# LeoBlinky2018.net
KiCad netlist of a schematic drawn in Altium Designer
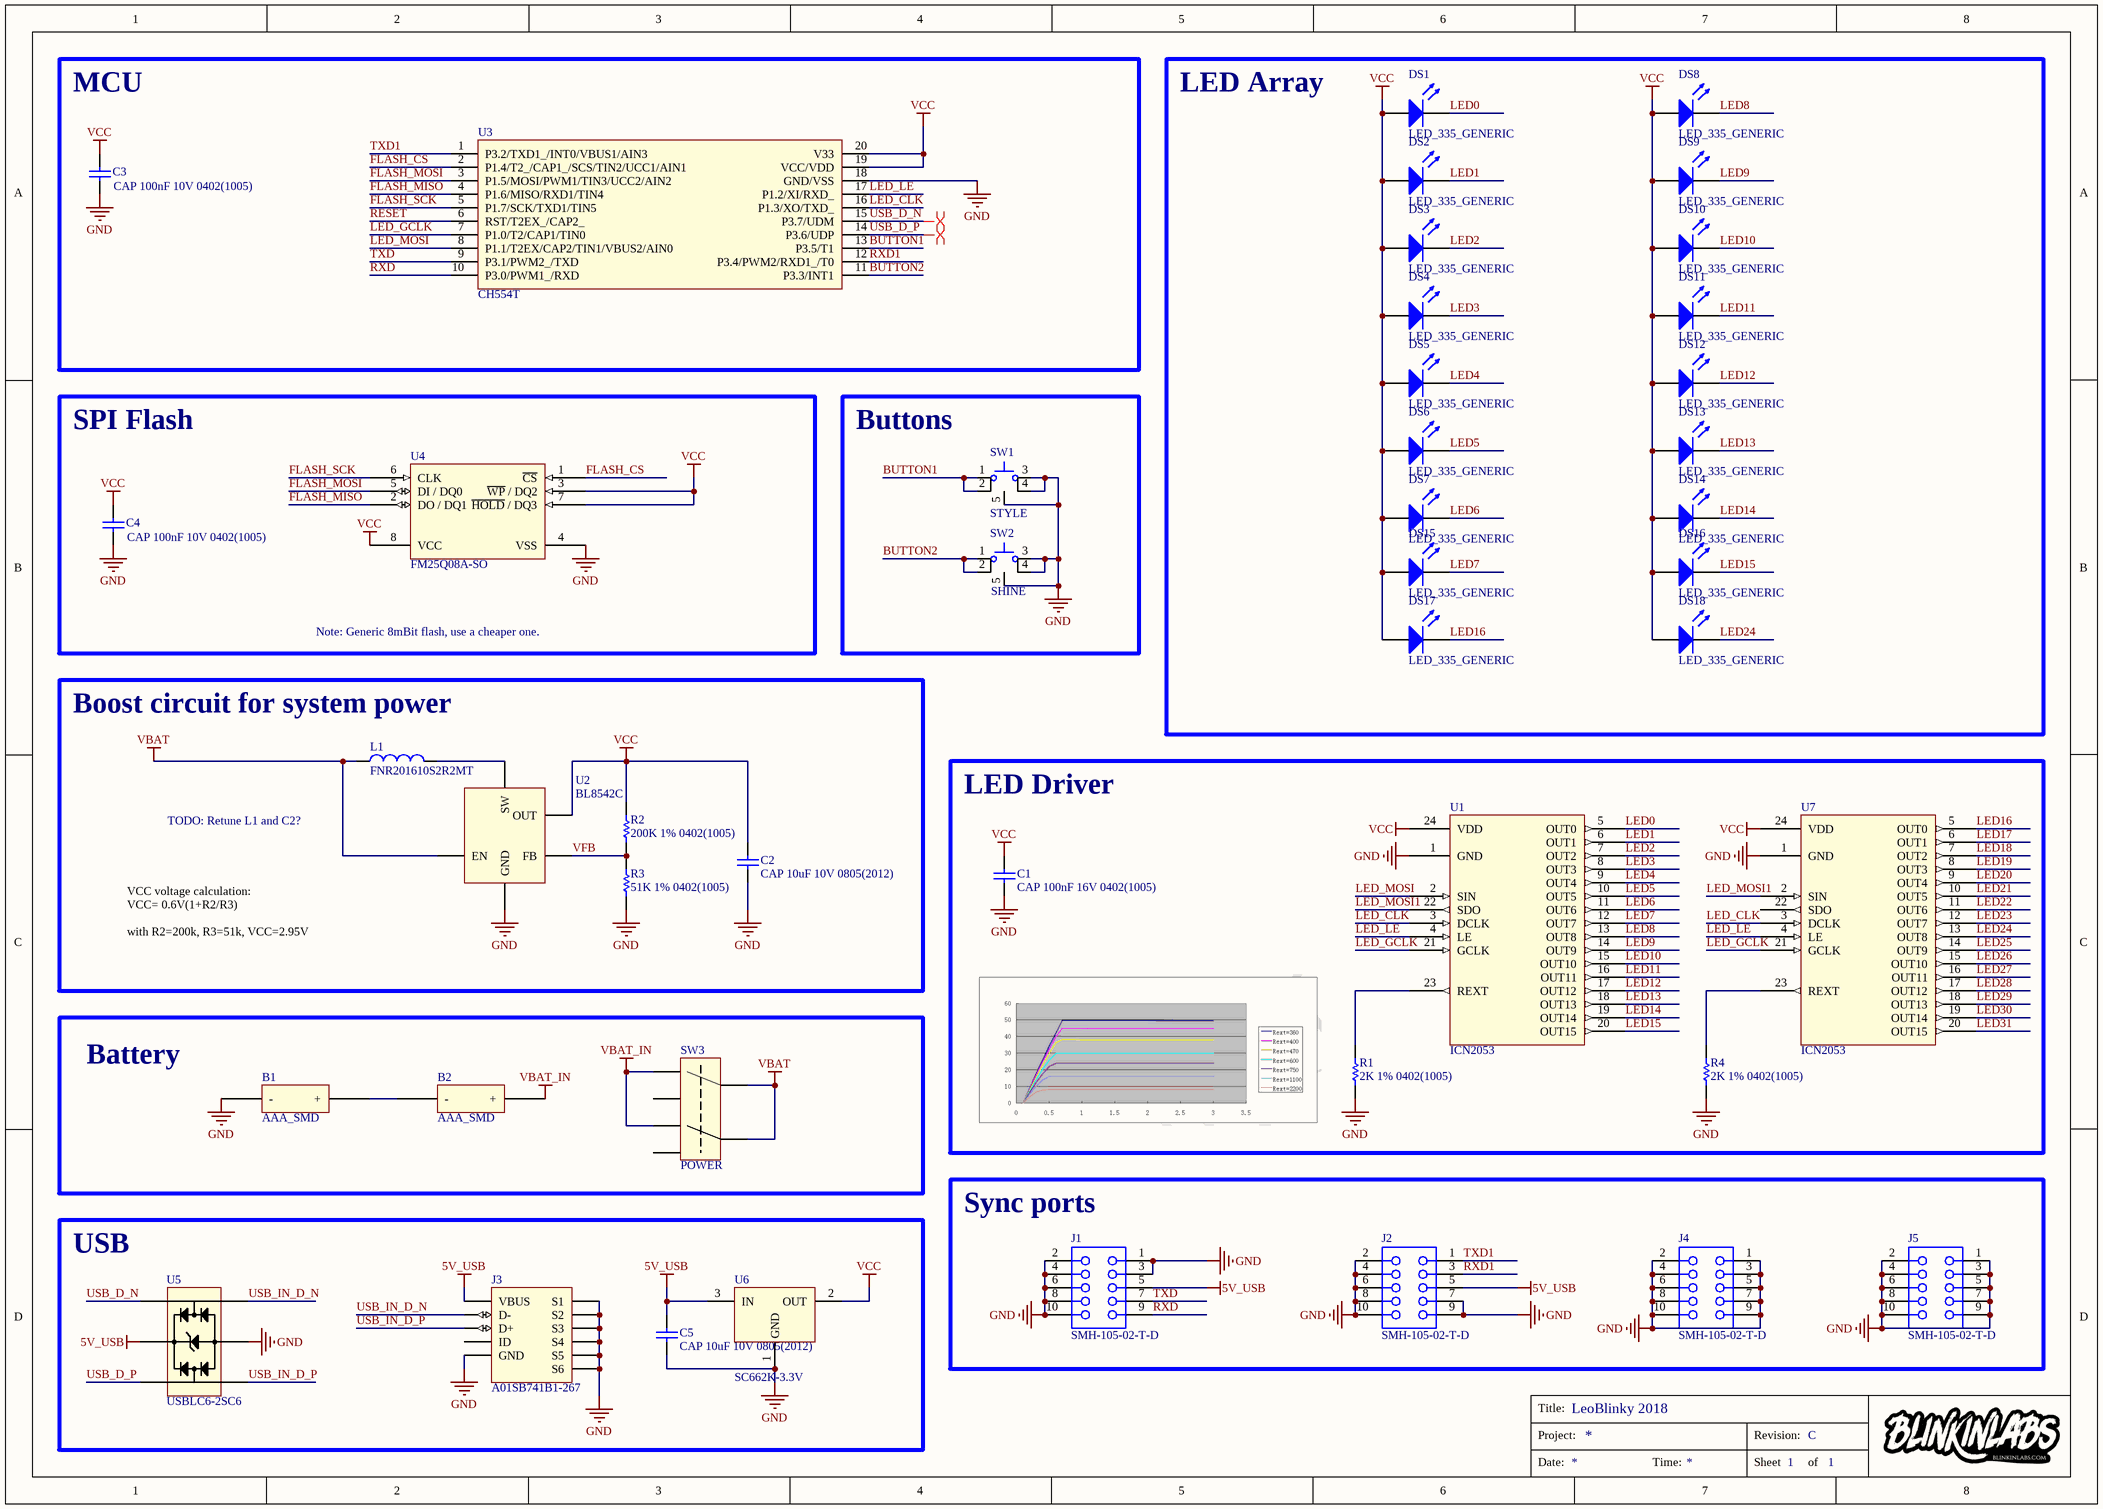
[diagram p0: LeoBlinky2018.SchDoc]

(export (version "E")
  (design (tool "Eeschema 10.0.6"))
  (components
    (comp (ref "B1")
      (value "AAA_SMD")
      (footprint "AAA_SMD")
      (description "AAA battery holder, surface mount.")
      (libsource (lib "Blinkinlabs") (part "AAA_SMD"))
    )
    (comp (ref "B2")
      (value "AAA_SMD")
      (footprint "AAA_SMD")
      (description "AAA battery holder, surface mount.")
      (libsource (lib "Blinkinlabs") (part "AAA_SMD"))
    )
    (comp (ref "C1")
      (value "CAP 100nF 16V 0402(1005)")
      (footprint "CAPC0402(1005)60_N")
      (description "CAP 100nF 16V -20% to +80% 0402 (1005 Metric) Thickness 0.6mm SMD")
      (fields (field (name "TOLERANCE") "-20% to +80%"))
      (libsource (lib "Altium Content Vault") (part "CAP"))
    )
    (comp (ref "C2")
      (value "CAP 10uF 10V 0805(2012)")
      (footprint "CAPC0805(2012)145_N")
      (description "CAP 10uF 10V ±10% 0805 (2012 Metric) Thickness 1.45mm SMD")
      (fields (field (name "TOLERANCE") "Â±10%"))
      (libsource (lib "Altium Content Vault") (part "CMP-1036-04922-1"))
    )
    (comp (ref "C3")
      (value "CAP 100nF 10V 0402(1005)")
      (footprint "CAPC0402(1005)60_L")
      (description "CAP 100nF 10V ±10% 0402 (1005 Metric) Thickness 0.6mm SMD")
      (fields (field (name "TOLERANCE") "Â±10%"))
      (libsource (lib "Altium Content Vault") (part "CMP-1034-02065-1"))
    )
    (comp (ref "C4")
      (value "CAP 100nF 10V 0402(1005)")
      (footprint "CAPC0402(1005)60_L")
      (description "CAP 100nF 10V ±10% 0402 (1005 Metric) Thickness 0.6mm SMD")
      (fields (field (name "TOLERANCE") "Â±10%"))
      (libsource (lib "Altium Content Vault") (part "CMP-1034-02065-1"))
    )
    (comp (ref "C5")
      (value "CAP 10uF 10V 0805(2012)")
      (footprint "CAPC0805(2012)145_N")
      (description "CAP 10uF 10V ±10% 0805 (2012 Metric) Thickness 1.45mm SMD")
      (fields (field (name "TOLERANCE") "Â±10%"))
      (libsource (lib "Altium Content Vault") (part "CAP"))
    )
    (comp (ref "DS1")
      (value "LED_335_GENERIC")
      (footprint "LED_335_GENERIC")
      (description "SMD LED, side visible, generic")
      (libsource (lib "Blinkinlabs") (part "LED_335_GENERIC"))
    )
    (comp (ref "DS2")
      (value "LED_335_GENERIC")
      (footprint "LED_335_GENERIC")
      (description "SMD LED, side visible, generic")
      (libsource (lib "Blinkinlabs") (part "LED_335_GENERIC"))
    )
    (comp (ref "DS3")
      (value "LED_335_GENERIC")
      (footprint "LED_335_GENERIC")
      (description "SMD LED, side visible, generic")
      (libsource (lib "Blinkinlabs") (part "LED_335_GENERIC"))
    )
    (comp (ref "DS4")
      (value "LED_335_GENERIC")
      (footprint "LED_335_GENERIC")
      (description "SMD LED, side visible, generic")
      (libsource (lib "Blinkinlabs") (part "LED_335_GENERIC"))
    )
    (comp (ref "DS5")
      (value "LED_335_GENERIC")
      (footprint "LED_335_GENERIC")
      (description "SMD LED, side visible, generic")
      (libsource (lib "Blinkinlabs") (part "LED_335_GENERIC"))
    )
    (comp (ref "DS6")
      (value "LED_335_GENERIC")
      (footprint "LED_335_GENERIC")
      (description "SMD LED, side visible, generic")
      (libsource (lib "Blinkinlabs") (part "LED_335_GENERIC"))
    )
    (comp (ref "DS7")
      (value "LED_335_GENERIC")
      (footprint "LED_335_GENERIC")
      (description "SMD LED, side visible, generic")
      (libsource (lib "Blinkinlabs") (part "LED_335_GENERIC"))
    )
    (comp (ref "DS8")
      (value "LED_335_GENERIC")
      (footprint "LED_335_GENERIC")
      (description "SMD LED, side visible, generic")
      (libsource (lib "Blinkinlabs") (part "LED_335_GENERIC"))
    )
    (comp (ref "DS9")
      (value "LED_335_GENERIC")
      (footprint "LED_335_GENERIC")
      (description "SMD LED, side visible, generic")
      (libsource (lib "Blinkinlabs") (part "LED_335_GENERIC"))
    )
    (comp (ref "DS10")
      (value "LED_335_GENERIC")
      (footprint "LED_335_GENERIC")
      (description "SMD LED, side visible, generic")
      (libsource (lib "Blinkinlabs") (part "LED_335_GENERIC"))
    )
    (comp (ref "DS11")
      (value "LED_335_GENERIC")
      (footprint "LED_335_GENERIC")
      (description "SMD LED, side visible, generic")
      (libsource (lib "Blinkinlabs") (part "LED_335_GENERIC"))
    )
    (comp (ref "DS12")
      (value "LED_335_GENERIC")
      (footprint "LED_335_GENERIC")
      (description "SMD LED, side visible, generic")
      (libsource (lib "Blinkinlabs") (part "LED_335_GENERIC"))
    )
    (comp (ref "DS13")
      (value "LED_335_GENERIC")
      (footprint "LED_335_GENERIC")
      (description "SMD LED, side visible, generic")
      (libsource (lib "Blinkinlabs") (part "LED_335_GENERIC"))
    )
    (comp (ref "DS14")
      (value "LED_335_GENERIC")
      (footprint "LED_335_GENERIC")
      (description "SMD LED, side visible, generic")
      (libsource (lib "Blinkinlabs") (part "LED_335_GENERIC"))
    )
    (comp (ref "DS15")
      (value "LED_335_GENERIC")
      (footprint "LED_335_GENERIC")
      (description "SMD LED, side visible, generic")
      (libsource (lib "Blinkinlabs") (part "LED_335_GENERIC"))
    )
    (comp (ref "DS16")
      (value "LED_335_GENERIC")
      (footprint "LED_335_GENERIC")
      (description "SMD LED, side visible, generic")
      (libsource (lib "Blinkinlabs") (part "LED_335_GENERIC"))
    )
    (comp (ref "DS17")
      (value "LED_335_GENERIC")
      (footprint "LED_335_GENERIC")
      (description "SMD LED, side visible, generic")
      (libsource (lib "Blinkinlabs") (part "LED_335_GENERIC"))
    )
    (comp (ref "DS18")
      (value "LED_335_GENERIC")
      (footprint "LED_335_GENERIC")
      (description "SMD LED, side visible, generic")
      (libsource (lib "Blinkinlabs") (part "LED_335_GENERIC"))
    )
    (comp (ref "J1")
      (value "SMH-105-02-T-D")
      (footprint "SMTC-SMH-105-02-X-D")
      (description "SMT Horizontal Socket, -55 to 105 degC, 2.54 mm Pitch, 10-Pin, Female, RoHS")
      (fields (field (name "MANUFACTURER") "Samtec"))
      (libsource (lib "Altium Content Vault") (part "SMTC-SMH-105-02-X-D-X"))
    )
    (comp (ref "J2")
      (value "SMH-105-02-T-D")
      (footprint "SMTC-SMH-105-02-X-D")
      (description "SMT Horizontal Socket, -55 to 105 degC, 2.54 mm Pitch, 10-Pin, Female, RoHS")
      (fields (field (name "MANUFACTURER") "Samtec"))
      (libsource (lib "Altium Content Vault") (part "SMTC-SMH-105-02-X-D-X"))
    )
    (comp (ref "J3")
      (value "A01SB741B1-267")
      (footprint "A01SB741B1-267")
      (description "Micro USB B type 四脚全插牛角")
      (libsource (lib "Blinkinlabs") (part "A01SB741B1-267"))
    )
    (comp (ref "J4")
      (value "SMH-105-02-T-D")
      (footprint "SMTC-SMH-105-02-X-D")
      (description "SMT Horizontal Socket, -55 to 105 degC, 2.54 mm Pitch, 10-Pin, Female, RoHS")
      (fields (field (name "MANUFACTURER") "Samtec"))
      (libsource (lib "Altium Content Vault") (part "SMTC-SMH-105-02-X-D-X"))
    )
    (comp (ref "J5")
      (value "SMH-105-02-T-D")
      (footprint "SMTC-SMH-105-02-X-D")
      (description "SMT Horizontal Socket, -55 to 105 degC, 2.54 mm Pitch, 10-Pin, Female, RoHS")
      (fields (field (name "MANUFACTURER") "Samtec"))
      (libsource (lib "Altium Content Vault") (part "SMTC-SMH-105-02-X-D-X"))
    )
    (comp (ref "L1")
      (value "FNR201610S2R2MT")
      (footprint "FNR201610S")
      (description "Wire Wound SMD Power Inductors 2.0×1.6×1.0 2.2uH")
      (libsource (lib "Blinkinlabs") (part "FNR201610S2R2MT"))
    )
    (comp (ref "R1")
      (value "2K 1% 0402(1005)")
      (footprint "RESC0402(1005)_N")
      (description "2K 0.063W 1% 0402 (1005 Metric)  SMD")
      (fields (field (name "POWER") "0.063 W") (field (name "TOLERANCE") "1 %"))
      (libsource (lib "Altium Content Vault") (part "RES"))
    )
    (comp (ref "R2")
      (value "200K 1% 0402(1005)")
      (footprint "RESC0402(1005)_L")
      (description "200K 0.063W 1% 0402 (1005 Metric)  SMD")
      (fields (field (name "TOLERANCE") "1 %") (field (name "POWER") "0.063 W"))
      (libsource (lib "Altium Content Vault") (part "RES"))
    )
    (comp (ref "R3")
      (value "51K 1% 0402(1005)")
      (footprint "RESC0402(1005)_L")
      (description "51K 0.063W 1% 0402 (1005 Metric)  SMD")
      (fields (field (name "TOLERANCE") "1 %") (field (name "POWER") "0.063 W"))
      (libsource (lib "Altium Content Vault") (part "RES"))
    )
    (comp (ref "R4")
      (value "2K 1% 0402(1005)")
      (footprint "RESC0402(1005)_N")
      (description "2K 0.063W 1% 0402 (1005 Metric)  SMD")
      (fields (field (name "POWER") "0.063 W") (field (name "TOLERANCE") "1 %"))
      (libsource (lib "Altium Content Vault") (part "RES"))
    )
    (comp (ref "SW1")
      (value "STYLE")
      (footprint "TD-07XB")
      (description "Tact Switch")
      (fields
        (field (name "MANUFACTURER") "ShenZhen XieJia Electronics Co Ltd")
        (field (name "PARTNUMBER") "TD-07XB")
      )
      (libsource (lib "Blinkinlabs") (part "TD-07XB"))
    )
    (comp (ref "SW2")
      (value "SHINE")
      (footprint "TD-07XB")
      (description "Tact Switch")
      (fields
        (field (name "MANUFACTURER") "ShenZhen XieJia Electronics Co Ltd")
        (field (name "PARTNUMBER") "TD-07XB")
      )
      (libsource (lib "Blinkinlabs") (part "TD-07XB"))
    )
    (comp (ref "SW3")
      (value "POWER")
      (footprint "MSK-1133-NOHOLE")
      (description "SMD micro toggle switch, 2 position, 2 circuit")
      (libsource (lib "Blinkinlabs") (part "MSK-1133"))
    )
    (comp (ref "U1")
      (value "ICN2053")
      (footprint "SOP64P600X175-24N")
      (description "16-Channel PWM Constant Current LED Sink Driver")
      (fields (field (name "MANUFACTURER") "ChipOne"))
      (libsource (lib "Blinkinlabs") (part "ICN2053"))
    )
    (comp (ref "U2")
      (value "BL8542C")
      (footprint "SOT95P280X130-5N")
      (description "0.85V startup, 1MHz, 300mA Iout,  Synchronous Boost Converter (adjustable output)")
      (fields (field (name "MANUFACTURER") "Belling"))
      (libsource (lib "Blinkinlabs") (part "BL8542C"))
    )
    (comp (ref "U3")
      (value "CH554T")
      (footprint "TSOP65P660X110-20N")
      (description "8-bit enhanced USB microcontroller")
      (fields (field (name "MANUFACTURER") "WCH"))
      (libsource (lib "Blinkinlabs") (part "CH554T"))
    )
    (comp (ref "U4")
      (value "FM25Q08A-SO")
      (footprint "SOP127P600X175-8N")
      (description "8M-BIT SERIAL FLASH MEMORY, 150mil width")
      (fields (field (name "MANUFACTURER") "Shanghai Fudan Microelectronics Group Company Limited"))
      (libsource (lib "Blinkinlabs") (part "FM25Q08A-SO"))
    )
    (comp (ref "U5")
      (value "USBLC6-2SC6")
      (footprint "SOT95P280X145-6N")
      (description "Very low capacitance ESD protection")
      (fields (field (name "MANUFACTURER") "STMicroelectronics"))
      (libsource (lib "Blinkinlabs") (part "USBLC6-2SC6"))
    )
    (comp (ref "U6")
      (value "SC662K-3.3V")
      (footprint "SOT95P230X117-3N")
      (description "3.3V, 250mA Low dropout voltage regulator IC")
      (libsource (lib "Blinkinlabs") (part "SC662K-3.3V"))
    )
    (comp (ref "U7")
      (value "ICN2053")
      (footprint "SOP64P600X175-24N")
      (description "16-Channel PWM Constant Current LED Sink Driver")
      (fields (field (name "MANUFACTURER") "ChipOne"))
      (libsource (lib "Blinkinlabs") (part "ICN2053"))
    )
  )
  (nets
    (net (code "1") (name "/BUTTON1") (class "Default")
      (node (ref "SW1") (pin "1") (pinfunction "1_1") (pintype "passive"))
      (node (ref "SW1") (pin "2") (pinfunction "2_2") (pintype "passive"))
      (node (ref "U3") (pin "13") (pinfunction "P3.5/T1_13") (pintype "passive"))
    )
    (net (code "2") (name "/BUTTON2") (class "Default")
      (node (ref "SW2") (pin "1") (pinfunction "1_1") (pintype "passive"))
      (node (ref "SW2") (pin "2") (pinfunction "2_2") (pintype "passive"))
      (node (ref "U3") (pin "11") (pinfunction "P3.3/INT1_11") (pintype "passive"))
    )
    (net (code "3") (name "/FLASH_CS") (class "Default")
      (node (ref "U3") (pin "2") (pinfunction "P1.4/T2_/CAP1_/SCS/TIN2/UCC1/AIN1_2") (pintype "passive"))
      (node (ref "U4") (pin "1") (pinfunction "~{CS}_1") (pintype "input"))
    )
    (net (code "4") (name "/FLASH_MISO") (class "Default")
      (node (ref "U3") (pin "4") (pinfunction "P1.6/MISO/RXD1/TIN4_4") (pintype "passive"))
      (node (ref "U4") (pin "2") (pinfunction "DO_/_DQ1_2") (pintype "bidirectional"))
    )
    (net (code "5") (name "/FLASH_MOSI") (class "Default")
      (node (ref "U3") (pin "3") (pinfunction "P1.5/MOSI/PWM1/TIN3/UCC2/AIN2_3") (pintype "passive"))
      (node (ref "U4") (pin "5") (pinfunction "DI_/_DQ0_5") (pintype "bidirectional"))
    )
    (net (code "6") (name "/FLASH_SCK") (class "Default")
      (node (ref "U3") (pin "5") (pinfunction "P1.7/SCK/TXD1/TIN5_5") (pintype "passive"))
      (node (ref "U4") (pin "6") (pinfunction "CLK_6") (pintype "input"))
    )
    (net (code "7") (name "/LED0") (class "Default")
      (node (ref "DS1") (pin "1") (pinfunction "1_1") (pintype "passive"))
      (node (ref "U1") (pin "5") (pinfunction "OUT0_5") (pintype "output"))
    )
    (net (code "8") (name "/LED1") (class "Default")
      (node (ref "DS2") (pin "1") (pinfunction "1_1") (pintype "passive"))
      (node (ref "U1") (pin "6") (pinfunction "OUT1_6") (pintype "output"))
    )
    (net (code "9") (name "/LED2") (class "Default")
      (node (ref "DS3") (pin "1") (pinfunction "1_1") (pintype "passive"))
      (node (ref "U1") (pin "7") (pinfunction "OUT2_7") (pintype "output"))
    )
    (net (code "10") (name "/LED3") (class "Default")
      (node (ref "DS4") (pin "1") (pinfunction "1_1") (pintype "passive"))
      (node (ref "U1") (pin "8") (pinfunction "OUT3_8") (pintype "output"))
    )
    (net (code "11") (name "/LED4") (class "Default")
      (node (ref "DS5") (pin "1") (pinfunction "1_1") (pintype "passive"))
      (node (ref "U1") (pin "9") (pinfunction "OUT4_9") (pintype "output"))
    )
    (net (code "12") (name "/LED5") (class "Default")
      (node (ref "DS6") (pin "1") (pinfunction "1_1") (pintype "passive"))
      (node (ref "U1") (pin "10") (pinfunction "OUT5_10") (pintype "output"))
    )
    (net (code "13") (name "/LED6") (class "Default")
      (node (ref "DS7") (pin "1") (pinfunction "1_1") (pintype "passive"))
      (node (ref "U1") (pin "11") (pinfunction "OUT6_11") (pintype "output"))
    )
    (net (code "14") (name "/LED7") (class "Default")
      (node (ref "DS15") (pin "1") (pinfunction "1_1") (pintype "passive"))
      (node (ref "U1") (pin "12") (pinfunction "OUT7_12") (pintype "output"))
    )
    (net (code "15") (name "/LED8") (class "Default")
      (node (ref "DS8") (pin "1") (pinfunction "1_1") (pintype "passive"))
      (node (ref "U1") (pin "13") (pinfunction "OUT8_13") (pintype "output"))
    )
    (net (code "16") (name "/LED9") (class "Default")
      (node (ref "DS9") (pin "1") (pinfunction "1_1") (pintype "passive"))
      (node (ref "U1") (pin "14") (pinfunction "OUT9_14") (pintype "output"))
    )
    (net (code "17") (name "/LED10") (class "Default")
      (node (ref "DS10") (pin "1") (pinfunction "1_1") (pintype "passive"))
      (node (ref "U1") (pin "15") (pinfunction "OUT10_15") (pintype "output"))
    )
    (net (code "18") (name "/LED11") (class "Default")
      (node (ref "DS11") (pin "1") (pinfunction "1_1") (pintype "passive"))
      (node (ref "U1") (pin "16") (pinfunction "OUT11_16") (pintype "output"))
    )
    (net (code "19") (name "/LED12") (class "Default")
      (node (ref "DS12") (pin "1") (pinfunction "1_1") (pintype "passive"))
      (node (ref "U1") (pin "17") (pinfunction "OUT12_17") (pintype "output"))
    )
    (net (code "20") (name "/LED13") (class "Default")
      (node (ref "DS13") (pin "1") (pinfunction "1_1") (pintype "passive"))
      (node (ref "U1") (pin "18") (pinfunction "OUT13_18") (pintype "output"))
    )
    (net (code "21") (name "/LED14") (class "Default")
      (node (ref "DS14") (pin "1") (pinfunction "1_1") (pintype "passive"))
      (node (ref "U1") (pin "19") (pinfunction "OUT14_19") (pintype "output"))
    )
    (net (code "22") (name "/LED15") (class "Default")
      (node (ref "DS16") (pin "1") (pinfunction "1_1") (pintype "passive"))
      (node (ref "U1") (pin "20") (pinfunction "OUT15_20") (pintype "output"))
    )
    (net (code "23") (name "/LED16") (class "Default")
      (node (ref "DS17") (pin "1") (pinfunction "1_1") (pintype "passive"))
      (node (ref "U7") (pin "5") (pinfunction "OUT0_5") (pintype "output"))
    )
    (net (code "24") (name "/LED17") (class "Default")
      (node (ref "U7") (pin "6") (pinfunction "OUT1_6") (pintype "output"))
    )
    (net (code "25") (name "/LED18") (class "Default")
      (node (ref "U7") (pin "7") (pinfunction "OUT2_7") (pintype "output"))
    )
    (net (code "26") (name "/LED19") (class "Default")
      (node (ref "U7") (pin "8") (pinfunction "OUT3_8") (pintype "output"))
    )
    (net (code "27") (name "/LED20") (class "Default")
      (node (ref "U7") (pin "9") (pinfunction "OUT4_9") (pintype "output"))
    )
    (net (code "28") (name "/LED21") (class "Default")
      (node (ref "U7") (pin "10") (pinfunction "OUT5_10") (pintype "output"))
    )
    (net (code "29") (name "/LED22") (class "Default")
      (node (ref "U7") (pin "11") (pinfunction "OUT6_11") (pintype "output"))
    )
    (net (code "30") (name "/LED23") (class "Default")
      (node (ref "U7") (pin "12") (pinfunction "OUT7_12") (pintype "output"))
    )
    (net (code "31") (name "/LED24") (class "Default")
      (node (ref "DS18") (pin "1") (pinfunction "1_1") (pintype "passive"))
      (node (ref "U7") (pin "13") (pinfunction "OUT8_13") (pintype "output"))
    )
    (net (code "32") (name "/LED25") (class "Default")
      (node (ref "U7") (pin "14") (pinfunction "OUT9_14") (pintype "output"))
    )
    (net (code "33") (name "/LED26") (class "Default")
      (node (ref "U7") (pin "15") (pinfunction "OUT10_15") (pintype "output"))
    )
    (net (code "34") (name "/LED27") (class "Default")
      (node (ref "U7") (pin "16") (pinfunction "OUT11_16") (pintype "output"))
    )
    (net (code "35") (name "/LED28") (class "Default")
      (node (ref "U7") (pin "17") (pinfunction "OUT12_17") (pintype "output"))
    )
    (net (code "36") (name "/LED29") (class "Default")
      (node (ref "U7") (pin "18") (pinfunction "OUT13_18") (pintype "output"))
    )
    (net (code "37") (name "/LED30") (class "Default")
      (node (ref "U7") (pin "19") (pinfunction "OUT14_19") (pintype "output"))
    )
    (net (code "38") (name "/LED31") (class "Default")
      (node (ref "U7") (pin "20") (pinfunction "OUT15_20") (pintype "output"))
    )
    (net (code "39") (name "/LED_CLK") (class "Default")
      (node (ref "U1") (pin "3") (pinfunction "DCLK_3") (pintype "input"))
      (node (ref "U3") (pin "16") (pinfunction "P1.3/XO/TXD__16") (pintype "passive"))
      (node (ref "U7") (pin "3") (pinfunction "DCLK_3") (pintype "input"))
    )
    (net (code "40") (name "/LED_GCLK") (class "Default")
      (node (ref "U1") (pin "21") (pinfunction "GCLK_21") (pintype "input"))
      (node (ref "U3") (pin "7") (pinfunction "P1.0/T2/CAP1/TIN0_7") (pintype "passive"))
      (node (ref "U7") (pin "21") (pinfunction "GCLK_21") (pintype "input"))
    )
    (net (code "41") (name "/LED_LE") (class "Default")
      (node (ref "U1") (pin "4") (pinfunction "LE_4") (pintype "input"))
      (node (ref "U3") (pin "17") (pinfunction "P1.2/XI/RXD__17") (pintype "passive"))
      (node (ref "U7") (pin "4") (pinfunction "LE_4") (pintype "input"))
    )
    (net (code "42") (name "/LED_MOSI") (class "Default")
      (node (ref "U1") (pin "2") (pinfunction "SIN_2") (pintype "input"))
      (node (ref "U3") (pin "8") (pinfunction "P1.1/T2EX/CAP2/TIN1/VBUS2/AIN0_8") (pintype "passive"))
    )
    (net (code "43") (name "/LED_MOSI1") (class "Default")
      (node (ref "U1") (pin "22") (pinfunction "SDO_22") (pintype "output"))
      (node (ref "U7") (pin "2") (pinfunction "SIN_2") (pintype "input"))
    )
    (net (code "44") (name "/RESET") (class "Default")
      (node (ref "U3") (pin "6") (pinfunction "RST/T2EX_/CAP2__6") (pintype "passive"))
    )
    (net (code "45") (name "/RXD") (class "Default")
      (node (ref "J1") (pin "9") (pinfunction "9_9") (pintype "passive"))
      (node (ref "U3") (pin "10") (pinfunction "P3.0/PWM1_/RXD_10") (pintype "passive"))
    )
    (net (code "46") (name "/RXD1") (class "Default")
      (node (ref "J2") (pin "3") (pinfunction "3_3") (pintype "passive"))
      (node (ref "U3") (pin "12") (pinfunction "P3.4/PWM2/RXD1_/T0_12") (pintype "passive"))
    )
    (net (code "47") (name "/TXD") (class "Default")
      (node (ref "J1") (pin "7") (pinfunction "7_7") (pintype "passive"))
      (node (ref "U3") (pin "9") (pinfunction "P3.1/PWM2_/TXD_9") (pintype "passive"))
    )
    (net (code "48") (name "/TXD1") (class "Default")
      (node (ref "J2") (pin "1") (pinfunction "1_1") (pintype "passive"))
      (node (ref "U3") (pin "1") (pinfunction "P3.2/TXD1_/INT0/VBUS1/AIN3_1") (pintype "passive"))
    )
    (net (code "49") (name "/USB_D_N") (class "Default")
      (node (ref "U3") (pin "15") (pinfunction "P3.7/UDM_15") (pintype "passive"))
      (node (ref "U5") (pin "4") (pinfunction "I/O2_4") (pintype "passive"))
    )
    (net (code "50") (name "/USB_D_P") (class "Default")
      (node (ref "U3") (pin "14") (pinfunction "P3.6/UDP_14") (pintype "passive"))
      (node (ref "U5") (pin "6") (pinfunction "I/O1_6") (pintype "passive"))
    )
    (net (code "51") (name "/USB_IN_D_N") (class "Default")
      (node (ref "J3") (pin "D-") (pinfunction "D-_D-") (pintype "bidirectional"))
      (node (ref "U5") (pin "3") (pinfunction "I/O2_3") (pintype "passive"))
    )
    (net (code "52") (name "/USB_IN_D_P") (class "Default")
      (node (ref "J3") (pin "D+") (pinfunction "D+_D+") (pintype "bidirectional"))
      (node (ref "U5") (pin "1") (pinfunction "I/O1_1") (pintype "passive"))
    )
    (net (code "53") (name "/VFB") (class "Default")
      (node (ref "R2") (pin "1") (pinfunction "1_1") (pintype "passive"))
      (node (ref "R3") (pin "2") (pinfunction "2_2") (pintype "passive"))
      (node (ref "U2") (pin "1") (pinfunction "FB_1") (pintype "passive"))
    )
    (net (code "54") (name "5V_USB") (class "Default")
      (node (ref "C5") (pin "2") (pinfunction "2_2") (pintype "passive"))
      (node (ref "J1") (pin "5") (pinfunction "5_5") (pintype "passive"))
      (node (ref "J2") (pin "5") (pinfunction "5_5") (pintype "passive"))
      (node (ref "J3") (pin "VBUS") (pinfunction "VBUS_VBUS") (pintype "power_in"))
      (node (ref "U5") (pin "5") (pinfunction "5_5") (pintype "passive"))
      (node (ref "U6") (pin "3") (pinfunction "IN_3") (pintype "power_in"))
    )
    (net (code "55") (name "GND") (class "Default")
      (node (ref "B1") (pin "2") (pinfunction "-_2") (pintype "power_in"))
      (node (ref "C1") (pin "1") (pinfunction "1_1") (pintype "passive"))
      (node (ref "C2") (pin "1") (pinfunction "1_1") (pintype "passive"))
      (node (ref "C3") (pin "1") (pinfunction "1_1") (pintype "passive"))
      (node (ref "C4") (pin "1") (pinfunction "1_1") (pintype "passive"))
      (node (ref "C5") (pin "1") (pinfunction "1_1") (pintype "passive"))
      (node (ref "J1") (pin "1") (pinfunction "1_1") (pintype "passive"))
      (node (ref "J1") (pin "10") (pinfunction "10_10") (pintype "passive"))
      (node (ref "J1") (pin "2") (pinfunction "2_2") (pintype "passive"))
      (node (ref "J1") (pin "3") (pinfunction "3_3") (pintype "passive"))
      (node (ref "J1") (pin "4") (pinfunction "4_4") (pintype "passive"))
      (node (ref "J1") (pin "6") (pinfunction "6_6") (pintype "passive"))
      (node (ref "J1") (pin "8") (pinfunction "8_8") (pintype "passive"))
      (node (ref "J2") (pin "10") (pinfunction "10_10") (pintype "passive"))
      (node (ref "J2") (pin "2") (pinfunction "2_2") (pintype "passive"))
      (node (ref "J2") (pin "4") (pinfunction "4_4") (pintype "passive"))
      (node (ref "J2") (pin "6") (pinfunction "6_6") (pintype "passive"))
      (node (ref "J2") (pin "7") (pinfunction "7_7") (pintype "passive"))
      (node (ref "J2") (pin "8") (pinfunction "8_8") (pintype "passive"))
      (node (ref "J2") (pin "9") (pinfunction "9_9") (pintype "passive"))
      (node (ref "J3") (pin "GND") (pinfunction "GND_GND") (pintype "power_in"))
      (node (ref "J3") (pin "S1") (pinfunction "S1_S1") (pintype "passive"))
      (node (ref "J3") (pin "S2") (pinfunction "S2_S2") (pintype "passive"))
      (node (ref "J3") (pin "S3") (pinfunction "S3_S3") (pintype "passive"))
      (node (ref "J3") (pin "S4") (pinfunction "S4_S4") (pintype "passive"))
      (node (ref "J3") (pin "S5") (pinfunction "S5_S5") (pintype "passive"))
      (node (ref "J3") (pin "S6") (pinfunction "S6_S6") (pintype "passive"))
      (node (ref "J4") (pin "1") (pinfunction "1_1") (pintype "passive"))
      (node (ref "J4") (pin "10") (pinfunction "10_10") (pintype "passive"))
      (node (ref "J4") (pin "2") (pinfunction "2_2") (pintype "passive"))
      (node (ref "J4") (pin "3") (pinfunction "3_3") (pintype "passive"))
      (node (ref "J4") (pin "4") (pinfunction "4_4") (pintype "passive"))
      (node (ref "J4") (pin "5") (pinfunction "5_5") (pintype "passive"))
      (node (ref "J4") (pin "6") (pinfunction "6_6") (pintype "passive"))
      (node (ref "J4") (pin "7") (pinfunction "7_7") (pintype "passive"))
      (node (ref "J4") (pin "8") (pinfunction "8_8") (pintype "passive"))
      (node (ref "J4") (pin "9") (pinfunction "9_9") (pintype "passive"))
      (node (ref "J5") (pin "1") (pinfunction "1_1") (pintype "passive"))
      (node (ref "J5") (pin "10") (pinfunction "10_10") (pintype "passive"))
      (node (ref "J5") (pin "2") (pinfunction "2_2") (pintype "passive"))
      (node (ref "J5") (pin "3") (pinfunction "3_3") (pintype "passive"))
      (node (ref "J5") (pin "4") (pinfunction "4_4") (pintype "passive"))
      (node (ref "J5") (pin "5") (pinfunction "5_5") (pintype "passive"))
      (node (ref "J5") (pin "6") (pinfunction "6_6") (pintype "passive"))
      (node (ref "J5") (pin "7") (pinfunction "7_7") (pintype "passive"))
      (node (ref "J5") (pin "8") (pinfunction "8_8") (pintype "passive"))
      (node (ref "J5") (pin "9") (pinfunction "9_9") (pintype "passive"))
      (node (ref "R1") (pin "1") (pinfunction "1_1") (pintype "passive"))
      (node (ref "R3") (pin "1") (pinfunction "1_1") (pintype "passive"))
      (node (ref "R4") (pin "1") (pinfunction "1_1") (pintype "passive"))
      (node (ref "SW1") (pin "3") (pinfunction "3_3") (pintype "passive"))
      (node (ref "SW1") (pin "4") (pinfunction "4_4") (pintype "passive"))
      (node (ref "SW1") (pin "5") (pinfunction "5_5") (pintype "passive"))
      (node (ref "SW2") (pin "3") (pinfunction "3_3") (pintype "passive"))
      (node (ref "SW2") (pin "4") (pinfunction "4_4") (pintype "passive"))
      (node (ref "SW2") (pin "5") (pinfunction "5_5") (pintype "passive"))
      (node (ref "U1") (pin "1") (pinfunction "GND_1") (pintype "power_in"))
      (node (ref "U2") (pin "2") (pinfunction "GND_2") (pintype "passive"))
      (node (ref "U3") (pin "18") (pinfunction "GND/VSS_18") (pintype "power_in"))
      (node (ref "U4") (pin "4") (pinfunction "VSS_4") (pintype "power_in"))
      (node (ref "U5") (pin "2") (pinfunction "GND_2") (pintype "passive"))
      (node (ref "U6") (pin "1") (pinfunction "GND_1") (pintype "power_in"))
      (node (ref "U7") (pin "1") (pinfunction "GND_1") (pintype "power_in"))
    )
    (net (code "56") (name "Net-(B1-+)") (class "Default")
      (node (ref "B1") (pin "1") (pinfunction "+_1") (pintype "power_in"))
      (node (ref "B2") (pin "2") (pinfunction "-_2") (pintype "power_in"))
    )
    (net (code "57") (name "Net-(U1-REXT)") (class "Default")
      (node (ref "R1") (pin "2") (pinfunction "2_2") (pintype "passive"))
      (node (ref "U1") (pin "23") (pinfunction "REXT_23") (pintype "output"))
    )
    (net (code "58") (name "Net-(U2-SW)") (class "Default")
      (node (ref "L1") (pin "2") (pinfunction "2_2") (pintype "passive"))
      (node (ref "U2") (pin "4") (pinfunction "SW_4") (pintype "passive"))
    )
    (net (code "59") (name "Net-(U7-REXT)") (class "Default")
      (node (ref "R4") (pin "2") (pinfunction "2_2") (pintype "passive"))
      (node (ref "U7") (pin "23") (pinfunction "REXT_23") (pintype "output"))
    )
    (net (code "60") (name "VBAT") (class "Default")
      (node (ref "L1") (pin "1") (pinfunction "1_1") (pintype "passive"))
      (node (ref "SW3") (pin "2") (pintype "passive"))
      (node (ref "SW3") (pin "5") (pintype "passive"))
      (node (ref "U2") (pin "3") (pinfunction "EN_3") (pintype "passive"))
    )
    (net (code "61") (name "VBAT_IN") (class "Default")
      (node (ref "B2") (pin "1") (pinfunction "+_1") (pintype "power_in"))
      (node (ref "SW3") (pin "1") (pinfunction "A_1") (pintype "passive"))
      (node (ref "SW3") (pin "6") (pintype "passive"))
    )
    (net (code "62") (name "VCC") (class "Default")
      (node (ref "C1") (pin "2") (pinfunction "2_2") (pintype "passive"))
      (node (ref "C2") (pin "2") (pinfunction "2_2") (pintype "passive"))
      (node (ref "C3") (pin "2") (pinfunction "2_2") (pintype "passive"))
      (node (ref "C4") (pin "2") (pinfunction "2_2") (pintype "passive"))
      (node (ref "DS1") (pin "2") (pinfunction "1_2") (pintype "passive"))
      (node (ref "DS10") (pin "2") (pinfunction "1_2") (pintype "passive"))
      (node (ref "DS11") (pin "2") (pinfunction "1_2") (pintype "passive"))
      (node (ref "DS12") (pin "2") (pinfunction "1_2") (pintype "passive"))
      (node (ref "DS13") (pin "2") (pinfunction "1_2") (pintype "passive"))
      (node (ref "DS14") (pin "2") (pinfunction "1_2") (pintype "passive"))
      (node (ref "DS15") (pin "2") (pinfunction "1_2") (pintype "passive"))
      (node (ref "DS16") (pin "2") (pinfunction "1_2") (pintype "passive"))
      (node (ref "DS17") (pin "2") (pinfunction "1_2") (pintype "passive"))
      (node (ref "DS18") (pin "2") (pinfunction "1_2") (pintype "passive"))
      (node (ref "DS2") (pin "2") (pinfunction "1_2") (pintype "passive"))
      (node (ref "DS3") (pin "2") (pinfunction "1_2") (pintype "passive"))
      (node (ref "DS4") (pin "2") (pinfunction "1_2") (pintype "passive"))
      (node (ref "DS5") (pin "2") (pinfunction "1_2") (pintype "passive"))
      (node (ref "DS6") (pin "2") (pinfunction "1_2") (pintype "passive"))
      (node (ref "DS7") (pin "2") (pinfunction "1_2") (pintype "passive"))
      (node (ref "DS8") (pin "2") (pinfunction "1_2") (pintype "passive"))
      (node (ref "DS9") (pin "2") (pinfunction "1_2") (pintype "passive"))
      (node (ref "R2") (pin "2") (pinfunction "2_2") (pintype "passive"))
      (node (ref "U1") (pin "24") (pinfunction "VDD_24") (pintype "power_in"))
      (node (ref "U2") (pin "5") (pinfunction "OUT_5") (pintype "passive"))
      (node (ref "U3") (pin "19") (pinfunction "VCC/VDD_19") (pintype "power_in"))
      (node (ref "U3") (pin "20") (pinfunction "V33_20") (pintype "power_in"))
      (node (ref "U4") (pin "3") (pinfunction "~{WP}_/_DQ2_3") (pintype "input"))
      (node (ref "U4") (pin "7") (pinfunction "~{HOLD}_/_DQ3_7") (pintype "input"))
      (node (ref "U4") (pin "8") (pinfunction "VCC_8") (pintype "power_in"))
      (node (ref "U6") (pin "2") (pinfunction "OUT_2") (pintype "power_in"))
      (node (ref "U7") (pin "24") (pinfunction "VDD_24") (pintype "power_in"))
    )
    (net (code "63") (name "unconnected-(J3-PadID)") (class "Default")
      (node (ref "J3") (pin "ID") (pinfunction "ID_ID") (pintype "passive"))
    )
    (net (code "64") (name "unconnected-(SW3-Pad3)") (class "Default")
      (node (ref "SW3") (pin "3") (pintype "passive"))
    )
    (net (code "65") (name "unconnected-(SW3-Pad4)") (class "Default")
      (node (ref "SW3") (pin "4") (pintype "passive"))
    )
    (net (code "66") (name "unconnected-(U7-SDO-Pad22)") (class "Default")
      (node (ref "U7") (pin "22") (pinfunction "SDO_22") (pintype "output"))
    )
  )
)
